# AmpliRF.net
KiCad netlist of a schematic drawn in Altium Designer
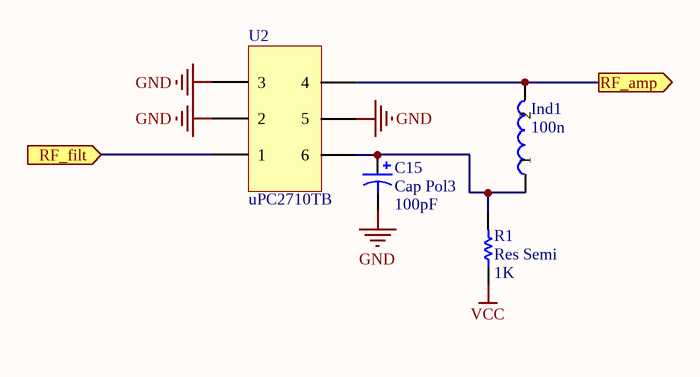
[diagram p0: AmpliRF.SchDoc]

(export (version "E")
  (design (tool "Eeschema 10.0.6"))
  (components
    (comp (ref "C15")
      (value "Cap Pol3")
      (footprint "C0805")
      (description "Polarized Capacitor (Surface Mount)")
      (fields (field (name "ALTIUM_VALUE") "100pF") (field (name "PUBLISHER") "Altium Limited"))
      (libsource (lib "Miscellaneous Devices") (part "Cap Pol3"))
    )
    (comp (ref "Ind1")
      (value "Ind2")
      (footprint "NTH12_2")
      (fields (field (name "VALOR") "100n"))
      (libsource (lib "epf") (part "Ind2"))
    )
    (comp (ref "R1")
      (value "Res Semi")
      (footprint "2012[0805]")
      (description "Semiconductor Resistor")
      (fields (field (name "ALTIUM_VALUE") "1K") (field (name "PUBLISHER") "Altium Limited"))
      (libsource (lib "Miscellaneous Devices") (part "Res Semi"))
    )
    (comp (ref "U2") (value "uPC2710TB") (footprint "UPC2710TB2") (libsource (lib "epf") (part "uPC2710TB")))
  )
  (nets
    (net (code "1") (name "/RF_amp") (class "Default")
      (node (ref "Ind1") (pin "2") (pinfunction "2_2") (pintype "passive"))
      (node (ref "U2") (pin "RF_OUT") (pinfunction "4_RF_OUT") (pintype "passive"))
    )
    (net (code "2") (name "/RF_filt") (class "Default")
      (node (ref "U2") (pin "RF_IN") (pinfunction "1_RF_IN") (pintype "passive"))
    )
    (net (code "3") (name "GND") (class "Default")
      (node (ref "C15") (pin "2") (pinfunction "2_2") (pintype "passive"))
      (node (ref "U2") (pin "GND1") (pinfunction "2_GND1") (pintype "passive"))
      (node (ref "U2") (pin "GND2") (pinfunction "3_GND2") (pintype "passive"))
      (node (ref "U2") (pin "GND3") (pinfunction "5_GND3") (pintype "passive"))
    )
    (net (code "4") (name "Net-(U2-6)") (class "Default")
      (node (ref "C15") (pin "1") (pinfunction "1_1") (pintype "passive"))
      (node (ref "Ind1") (pin "1") (pinfunction "1_1") (pintype "passive"))
      (node (ref "R1") (pin "2") (pinfunction "2_2") (pintype "passive"))
      (node (ref "U2") (pin "Vcc") (pinfunction "6_Vcc") (pintype "passive"))
    )
    (net (code "5") (name "VCC") (class "Default")
      (node (ref "R1") (pin "1") (pinfunction "1_1") (pintype "passive"))
    )
  )
)
